# working.net
KiCad netlist of a schematic drawn in EAGLE
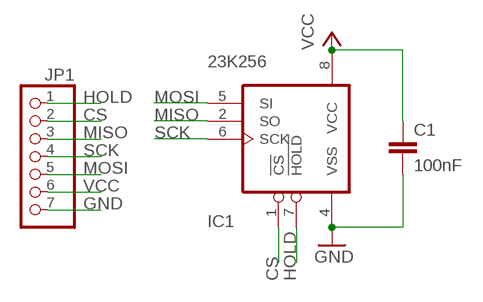
[diagram p0: schematic, sheet 1]

(export (version "E")
  (design (tool "Eeschema 10.0.6"))
  (components
    (comp (ref "C1")
      (value "100nF")
      (footprint "eagle-import:C805")
      (libsource (lib "eagle-import") (part "CAPC805"))
    )
    (comp (ref "IC1")
      (value "23K256")
      (footprint "eagle-import:SOIC8")
      (libsource (lib "eagle-import") (part "23K256"))
    )
    (comp (ref "JP1")
      (value "PINHD-1X7")
      (footprint "eagle-import:1X07")
      (libsource (lib "eagle-import") (part "PINHD-1X7"))
    )
  )
  (nets
    (net (code "1") (name "/CS") (class "Default")
      (node (ref "IC1") (pin "1") (pinfunction "~{CS}_1") (pintype "input"))
      (node (ref "JP1") (pin "2") (pinfunction "2_2") (pintype "passive"))
    )
    (net (code "2") (name "/HOLD") (class "Default")
      (node (ref "IC1") (pin "7") (pinfunction "~{HOLD}_7") (pintype "input"))
      (node (ref "JP1") (pin "1") (pinfunction "1_1") (pintype "passive"))
    )
    (net (code "3") (name "/MISO") (class "Default")
      (node (ref "IC1") (pin "2") (pinfunction "SO_2") (pintype "output"))
      (node (ref "JP1") (pin "3") (pinfunction "3_3") (pintype "passive"))
    )
    (net (code "4") (name "/MOSI") (class "Default")
      (node (ref "IC1") (pin "5") (pinfunction "SI_5") (pintype "input"))
      (node (ref "JP1") (pin "5") (pinfunction "5_5") (pintype "passive"))
    )
    (net (code "5") (name "/SCK") (class "Default")
      (node (ref "IC1") (pin "6") (pinfunction "SCK_6") (pintype "input"))
      (node (ref "JP1") (pin "4") (pinfunction "4_4") (pintype "passive"))
    )
    (net (code "6") (name "GND") (class "Default")
      (node (ref "C1") (pin "2") (pinfunction "2_2") (pintype "passive"))
      (node (ref "IC1") (pin "4") (pinfunction "VSS_4") (pintype "power_in"))
      (node (ref "JP1") (pin "7") (pinfunction "7_7") (pintype "passive"))
    )
    (net (code "7") (name "VCC") (class "Default")
      (node (ref "C1") (pin "1") (pinfunction "1_1") (pintype "passive"))
      (node (ref "IC1") (pin "8") (pinfunction "VCC_8") (pintype "power_in"))
      (node (ref "JP1") (pin "6") (pinfunction "6_6") (pintype "passive"))
    )
  )
)
